# Sheet1.net
KiCad netlist of a schematic drawn in Altium Designer
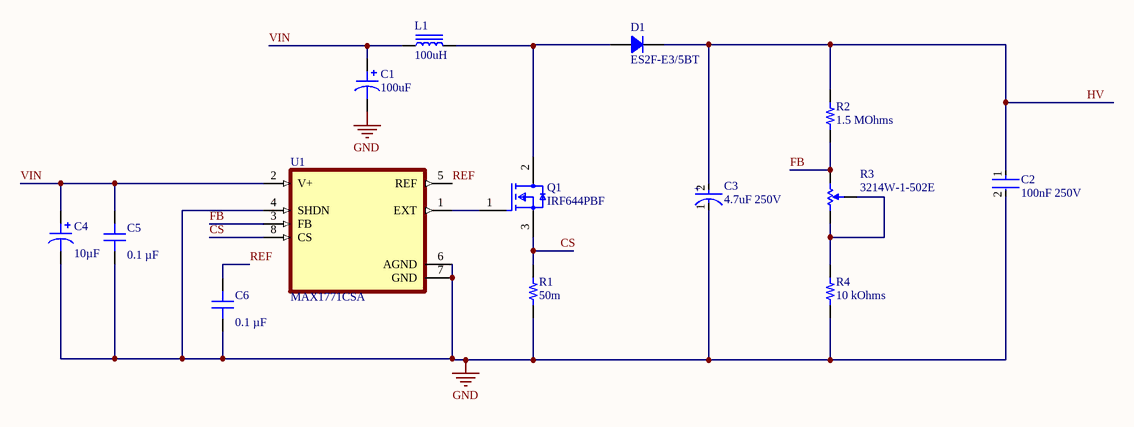
[diagram p0: Sheet1.SchDoc]

(export (version "E")
  (design (tool "Eeschema 10.0.6"))
  (components
    (comp (ref "C1")
      (value "100uF")
      (footprint "CAP ALSMD 8.3MM H10.5MM")
      (description "CAP ALUM 100UF 20% 35V SMD")
      (fields (field (name "PART NUMBER") "35SKV100M8X10.5"))
      (libsource (lib "Celestial Altium Library - altium_library") (part "Polarised Capacitor"))
    )
    (comp (ref "C2")
      (value "100nF 250V")
      (footprint "FP-0805-L_2_01_0_2-W_1_25-IPC_B")
      (description "CGA4J3X7T2E104K125AA")
      (fields (field (name "TOLERANCE") "10%") (field (name "VOLTAGE") "200V"))
      (libsource (lib "Altium Content Vault") (part "02cd4be3c70576c341d710602a673aa"))
    )
    (comp (ref "C3")
      (value "4.7uF 250V")
      (footprint "FP-RAD-TH-D_8_0_5-L_11_5-MFG")
      (description "A759KS475M2EBAE496")
      (fields (field (name "TOLERANCE") "20%"))
      (libsource (lib "Altium Content Vault") (part "203bc49f2ac43e59fd269a8c329ed05"))
    )
    (comp (ref "C4")
      (value "10µF")
      (footprint "CAP POL 1206_3216")
      (description "CAP TANT 10UF 20% 25V 1206")
      (fields (field (name "PART NUMBER") "F951E106MAAAQ2") (field (name "MANUFACTURER") "AVX Corporation"))
      (libsource (lib "Celestial Altium Library - altium_library") (part "Polarised Capacitor"))
    )
    (comp (ref "C5")
      (value "0.1 µF")
      (footprint "CAP 0402_1005")
      (description "CAP CER 0.1UF 35V X7R 0402")
      (fields (field (name "PART NUMBER") "CGA2B3X7R1V104M050BB"))
      (libsource (lib "Celestial Altium Library - altium_library") (part "Capacitor"))
    )
    (comp (ref "C6")
      (value "0.1 µF")
      (footprint "CAP 0402_1005")
      (description "CAP CER 0.1UF 35V X7R 0402")
      (fields (field (name "PART NUMBER") "CGA2B3X7R1V104M050BB"))
      (libsource (lib "Celestial Altium Library - altium_library") (part "Capacitor"))
    )
    (comp (ref "D1")
      (value "ES2F-E3/5BT")
      (footprint "DO214AA SMB")
      (description "DIODE GEN PURP 300V 2A DO214AA")
      (libsource (lib "Celestial Altium Library - altium_library") (part "Diode"))
    )
    (comp (ref "L1")
      (value "100uH")
      (footprint "BOURNS SRR1280")
      (description "FIXED IND 100UH 2.1A 150MOHM SMD")
      (fields (field (name "PART NUMBER") "SRR1280-101M"))
      (libsource (lib "Celestial Altium Library - altium_library") (part "Inductor"))
    )
    (comp (ref "Q1")
      (value "IRF644PBF")
      (footprint "FP-E21-0621-MFG")
      (description "N-MOSFET; unipolarny; 250V; 8,5A; 125W; TO220AB")
      (libsource (lib "Altium Content Vault") (part "277670f45256a45703965f138927d09"))
    )
    (comp (ref "R1")
      (value "50m")
      (footprint "RES 2512_6432")
      (description "RES 50M OHM 1% 1W 2512")
      (fields (field (name "PART NUMBER") "UR73D3ATTE50L0F"))
      (libsource (lib "Celestial Altium Library - altium_library") (part "Resistor"))
    )
    (comp (ref "R2")
      (value "1.5 MOhms")
      (footprint "RES 1206_3216")
      (description "ESR18EZPF1504")
      (fields (field (name "PART NUMBER") "CRCW12061M50JNEA") (field (name "MANUFACTURER") "Vishay Dale"))
      (libsource (lib "Celestial Altium Library - altium_library") (part "Resistor"))
    )
    (comp (ref "R3")
      (value "3214W-1-502E")
      (footprint "BOUR-3214W_V")
      (fields (field (name "MANUFACTURER") "Bourns"))
      (libsource (lib "Altium Content Vault") (part "RES-ADJ-3_A"))
    )
    (comp (ref "R4")
      (value "10 kOhms")
      (footprint "RES 0805_2012")
      (description "RES SMD 10K OHM 0.1% 1/10W 0805")
      (fields
        (field (name "PART NUMBER") "CPF0805B10KE")
        (field (name "MANUFACTURER") "TE Connectivity Passive Product")
      )
      (libsource (lib "Celestial Altium Library - altium_library") (part "Resistor"))
    )
    (comp (ref "U1")
      (value "MAX1771CSA")
      (footprint "SOIC127P600X175-8N:SOIC127P600X175-8N")
      (fields (field (name "MF") "Maxim Integrated"))
      (libsource (lib "MAX1771CSA") (part "MAX1771CSA"))
    )
  )
  (nets
    (net (code "1") (name "/CS") (class "Default")
      (node (ref "Q1") (pin "3") (pinfunction "S_3") (pintype "passive"))
      (node (ref "R1") (pin "2") (pinfunction "2_2") (pintype "passive"))
      (node (ref "U1") (pin "8") (pinfunction "CS_8") (pintype "input"))
    )
    (net (code "2") (name "/FB") (class "Default")
      (node (ref "R2") (pin "1") (pinfunction "1_1") (pintype "passive"))
      (node (ref "R3") (pin "3") (pinfunction "3_3") (pintype "passive"))
      (node (ref "U1") (pin "3") (pinfunction "FB_3") (pintype "input"))
    )
    (net (code "3") (name "/HV") (class "Default")
      (node (ref "C2") (pin "1") (pinfunction "1_1") (pintype "passive"))
      (node (ref "C3") (pin "2") (pinfunction "A_2") (pintype "passive"))
      (node (ref "D1") (pin "2") (pinfunction "2_2") (pintype "passive"))
      (node (ref "R2") (pin "2") (pinfunction "2_2") (pintype "passive"))
    )
    (net (code "4") (name "/REF") (class "Default")
      (node (ref "C6") (pin "2") (pinfunction "2_2") (pintype "passive"))
      (node (ref "U1") (pin "5") (pinfunction "REF_5") (pintype "output"))
    )
    (net (code "5") (name "/VIN") (class "Default")
      (node (ref "C1") (pin "1") (pinfunction "1_1") (pintype "passive"))
      (node (ref "C4") (pin "1") (pinfunction "1_1") (pintype "passive"))
      (node (ref "C5") (pin "2") (pinfunction "2_2") (pintype "passive"))
      (node (ref "L1") (pin "1") (pinfunction "1_1") (pintype "passive"))
      (node (ref "U1") (pin "2") (pinfunction "V+_2") (pintype "input"))
    )
    (net (code "6") (name "GND") (class "Default")
      (node (ref "C1") (pin "2") (pinfunction "2_2") (pintype "passive"))
      (node (ref "C2") (pin "2") (pinfunction "2_2") (pintype "passive"))
      (node (ref "C3") (pin "1") (pinfunction "C_1") (pintype "passive"))
      (node (ref "C4") (pin "2") (pinfunction "2_2") (pintype "passive"))
      (node (ref "C5") (pin "1") (pinfunction "1_1") (pintype "passive"))
      (node (ref "C6") (pin "1") (pinfunction "1_1") (pintype "passive"))
      (node (ref "R1") (pin "1") (pinfunction "1_1") (pintype "passive"))
      (node (ref "R4") (pin "1") (pinfunction "1_1") (pintype "passive"))
      (node (ref "U1") (pin "4") (pinfunction "SHDN_4") (pintype "input"))
      (node (ref "U1") (pin "6") (pinfunction "AGND_6") (pintype "power_in"))
      (node (ref "U1") (pin "7") (pinfunction "GND_7") (pintype "power_in"))
    )
    (net (code "7") (name "Net-(Q1-D)") (class "Default")
      (node (ref "D1") (pin "1") (pinfunction "1_1") (pintype "passive"))
      (node (ref "L1") (pin "2") (pinfunction "2_2") (pintype "passive"))
      (node (ref "Q1") (pin "2") (pinfunction "D_2") (pintype "passive"))
    )
    (net (code "8") (name "Net-(Q1-G)") (class "Default")
      (node (ref "Q1") (pin "1") (pinfunction "G_1") (pintype "passive"))
      (node (ref "U1") (pin "1") (pinfunction "EXT_1") (pintype "output"))
    )
    (net (code "9") (name "Net-(R3-Pad1)") (class "Default")
      (node (ref "R3") (pin "1") (pinfunction "1_1") (pintype "passive"))
      (node (ref "R3") (pin "2") (pinfunction "2_2") (pintype "passive"))
      (node (ref "R4") (pin "2") (pinfunction "2_2") (pintype "passive"))
    )
  )
)
